# Sheet_B1.net
KiCad netlist of a schematic drawn in Altium Designer
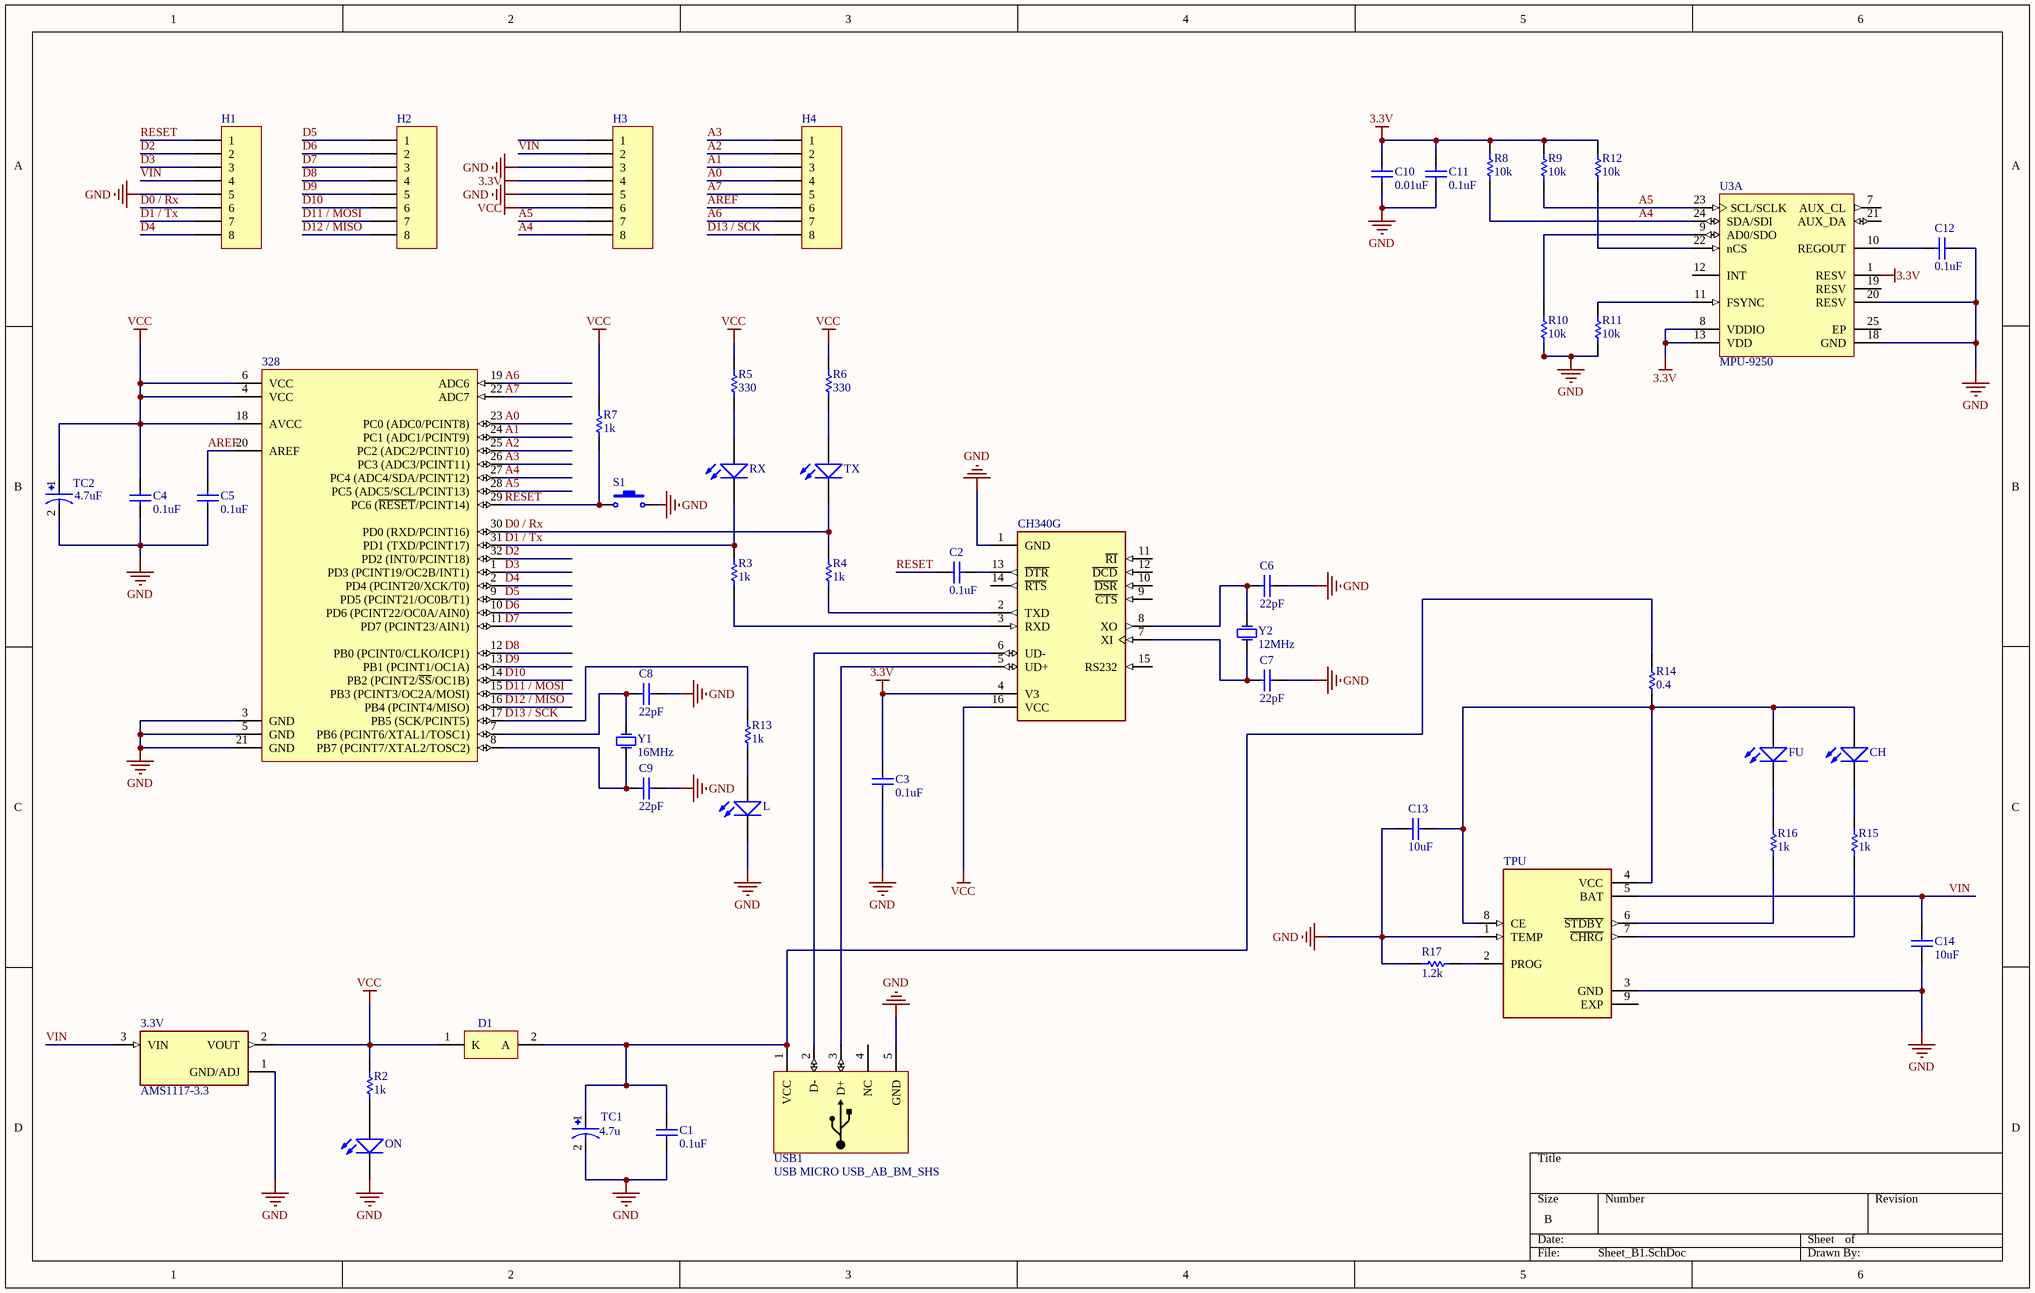
[diagram p0: Sheet_B1.SchDoc]

(export (version "E")
  (design (tool "Eeschema 10.0.6"))
  (components
    (comp (ref "3.3V")
      (value "AMS1117-3.3")
      (footprint "SOT229P700X180-4N")
      (description "Sot223/Pkg 1-Amp 3.3-Volt Low Drop Out Voltage Regulatator")
      (fields (field (name "MF") "Advanced Monolithic Systems"))
      (libsource (lib "AMS1117-3.3") (part "AMS1117-3.3"))
    )
    (comp (ref "328")
      (value "~")
      (footprint "32A_L")
      (libsource (lib "Altium Content Vault") (part "MC-8B-ATM48-SQ32"))
    )
    (comp (ref "C1")
      (value "0.1uF")
      (footprint "CAP0805")
      (description "CAP0805")
      (libsource (lib "CAP0805") (part "CAP0805"))
    )
    (comp (ref "C2")
      (value "0.1uF")
      (footprint "CAP0805")
      (description "CAP0805")
      (libsource (lib "CAP0805") (part "CAP0805"))
    )
    (comp (ref "C3")
      (value "0.1uF")
      (footprint "CAP0805")
      (description "CAP0805")
      (libsource (lib "CAP0805") (part "CAP0805"))
    )
    (comp (ref "C4")
      (value "0.1uF")
      (footprint "CAP0805")
      (description "CAP0805")
      (libsource (lib "CAP0805") (part "CAP0805"))
    )
    (comp (ref "C5")
      (value "0.1uF")
      (footprint "CAP0805")
      (description "CAP0805")
      (libsource (lib "CAP0805") (part "CAP0805"))
    )
    (comp (ref "C6")
      (value "22pF")
      (footprint "CAP0805")
      (description "CAP0805")
      (libsource (lib "CAP0805") (part "CAP0805"))
    )
    (comp (ref "C7")
      (value "22pF")
      (footprint "CAP0805")
      (description "CAP0805")
      (libsource (lib "CAP0805") (part "CAP0805"))
    )
    (comp (ref "C8")
      (value "22pF")
      (footprint "CAP0805")
      (description "CAP0805")
      (libsource (lib "CAP0805") (part "CAP0805"))
    )
    (comp (ref "C9")
      (value "22pF")
      (footprint "CAP0805")
      (description "CAP0805")
      (libsource (lib "CAP0805") (part "CAP0805"))
    )
    (comp (ref "C10")
      (value "0.01uF")
      (footprint "CAP0805")
      (description "CAP0805")
      (libsource (lib "CAP0805") (part "CAP0805"))
    )
    (comp (ref "C11")
      (value "0.1uF")
      (footprint "CAP0805")
      (description "CAP0805")
      (libsource (lib "CAP0805") (part "CAP0805"))
    )
    (comp (ref "C12")
      (value "0.1uF")
      (footprint "CAP0805")
      (description "CAP0805")
      (libsource (lib "CAP0805") (part "CAP0805"))
    )
    (comp (ref "C13")
      (value "10uF")
      (footprint "CAP0805")
      (description "CAP0805")
      (libsource (lib "CAP0805") (part "CAP0805"))
    )
    (comp (ref "C14")
      (value "10uF")
      (footprint "CAP0805")
      (description "CAP0805")
      (libsource (lib "CAP0805") (part "CAP0805"))
    )
    (comp (ref "CH")
      (value "~")
      (footprint "LED_SMD_0805")
      (libsource (lib "LED_SMD_0805") (part "LED_SMD_0805"))
    )
    (comp (ref "CH340G")
      (value "~")
      (footprint "SOIC127P600X180-16N")
      (description "USB Interface Integrated Circuit")
      (fields (field (name "MP") "Ch340G") (field (name "MF") "WCH"))
      (libsource (lib "CH340G") (part "CH340G"))
    )
    (comp (ref "D1")
      (value "~")
      (footprint "ONSC-SMB-2-403A-03_V")
      (description "Schottky Power Rectifier, 2-Pin SMB, Pb-Free, Tape and Reel")
      (fields (field (name "MANUFACTURER") "On Semiconductor") (field (name "PARTNUMBER") "SS24T3G"))
      (libsource (lib "Altium Content Vault") (part "ONSC-D-K1A2-2_A"))
    )
    (comp (ref "FU")
      (value "~")
      (footprint "LED_SMD_0805")
      (libsource (lib "LED_SMD_0805") (part "LED_SMD_0805"))
    )
    (comp (ref "H1") (value "~") (footprint "Header 8") (libsource (lib "Header 8") (part "Header 8")))
    (comp (ref "H2") (value "~") (footprint "Header 8") (libsource (lib "Header 8") (part "Header 8")))
    (comp (ref "H3") (value "~") (footprint "Header 8") (libsource (lib "Header 8") (part "Header 8")))
    (comp (ref "H4") (value "~") (footprint "Header 8") (libsource (lib "Header 8") (part "Header 8")))
    (comp (ref "L")
      (value "~")
      (footprint "LED_SMD_0805")
      (libsource (lib "LED_SMD_0805") (part "LED_SMD_0805"))
    )
    (comp (ref "ON")
      (value "~")
      (footprint "LED_SMD_0805")
      (libsource (lib "LED_SMD_0805") (part "LED_SMD_0805"))
    )
    (comp (ref "R2")
      (value "1k")
      (footprint "RES0805")
      (description "RES0805")
      (libsource (lib "RES0805") (part "RES0805"))
    )
    (comp (ref "R3")
      (value "1k")
      (footprint "RES0805")
      (description "RES0805")
      (libsource (lib "RES0805") (part "RES0805"))
    )
    (comp (ref "R4")
      (value "1k")
      (footprint "RES0805")
      (description "RES0805")
      (libsource (lib "RES0805") (part "RES0805"))
    )
    (comp (ref "R5")
      (value "330")
      (footprint "RES0805")
      (description "RES0805")
      (libsource (lib "RES0805") (part "RES0805"))
    )
    (comp (ref "R6")
      (value "330")
      (footprint "RES0805")
      (description "RES0805")
      (libsource (lib "RES0805") (part "RES0805"))
    )
    (comp (ref "R7")
      (value "1k")
      (footprint "RES0805")
      (description "RES0805")
      (libsource (lib "RES0805") (part "RES0805"))
    )
    (comp (ref "R8")
      (value "10k")
      (footprint "RES0805")
      (description "RES0805")
      (libsource (lib "RES0805") (part "RES0805"))
    )
    (comp (ref "R9")
      (value "10k")
      (footprint "RES0805")
      (description "RES0805")
      (libsource (lib "RES0805") (part "RES0805"))
    )
    (comp (ref "R10")
      (value "10k")
      (footprint "RES0805")
      (description "RES0805")
      (libsource (lib "RES0805") (part "RES0805"))
    )
    (comp (ref "R11")
      (value "10k")
      (footprint "RES0805")
      (description "RES0805")
      (libsource (lib "RES0805") (part "RES0805"))
    )
    (comp (ref "R12")
      (value "10k")
      (footprint "RES0805")
      (description "RES0805")
      (libsource (lib "RES0805") (part "RES0805"))
    )
    (comp (ref "R13")
      (value "1k")
      (footprint "RES0805")
      (description "RES0805")
      (libsource (lib "RES0805") (part "RES0805"))
    )
    (comp (ref "R14")
      (value "0.4")
      (footprint "RES0805")
      (description "RES0805")
      (libsource (lib "RES0805") (part "RES0805"))
    )
    (comp (ref "R15")
      (value "1k")
      (footprint "RES0805")
      (description "RES0805")
      (libsource (lib "RES0805") (part "RES0805"))
    )
    (comp (ref "R16")
      (value "1k")
      (footprint "RES0805")
      (description "RES0805")
      (libsource (lib "RES0805") (part "RES0805"))
    )
    (comp (ref "R17")
      (value "1.2k")
      (footprint "RES0805")
      (description "RES0805")
      (libsource (lib "RES0805") (part "RES0805"))
    )
    (comp (ref "RX")
      (value "~")
      (footprint "LED_SMD_0805")
      (libsource (lib "LED_SMD_0805") (part "LED_SMD_0805"))
    )
    (comp (ref "S1")
      (value "~")
      (footprint "Push Button Switch SMD")
      (libsource (lib "Push Button Switch SMD") (part "Push Button Switch SMD"))
    )
    (comp (ref "TC1")
      (value "4.7u")
      (footprint "CAPMP3516X190N")
      (description "4.7 ÂµF Molded Tantalum Capacitors 25 V 1411 (3528 Metric), 1210 1.5Ohm")
      (fields (field (name "MP") "TAJB475K025RNJ") (field (name "MF") "AVX"))
      (libsource (lib "TAJB475K025RNJ") (part "TAJB475K025RNJ"))
    )
    (comp (ref "TC2")
      (value "4.7uF")
      (footprint "CAPMP3516X190N")
      (description "4.7 ÂµF Molded Tantalum Capacitors 25 V 1411 (3528 Metric), 1210 1.5Ohm")
      (fields (field (name "MP") "TAJB475K025RNJ") (field (name "MF") "AVX"))
      (libsource (lib "TAJB475K025RNJ") (part "TAJB475K025RNJ"))
    )
    (comp (ref "TPU")
      (value "~")
      (footprint "SOIC127P600X175-9N")
      (description "TP4056-42-ESOP8 TP")
      (fields (field (name "MF") "Lite-On Semiconductor") (field (name "MP") "TP4056-42-ESOP8"))
      (libsource (lib "TP4056-42-ESOP8") (part "TP4056-42-ESOP8"))
    )
    (comp (ref "TX")
      (value "~")
      (footprint "LED_SMD_0805")
      (libsource (lib "LED_SMD_0805") (part "LED_SMD_0805"))
    )
    (comp (ref "U3")
      (value "MPU-9250")
      (footprint "INSE-QFN-24-1700X1540TP_M")
      (description "9-axis MotionTracking device, 2.4 to 3,6 V, -40 to 85 degC, 24-Pin QFN, RoHS, Tape and Reel")
      (fields (field (name "MANUFACTURER") "InvenSense"))
      (libsource (lib "Altium Content Vault") (part "INSE-MPU-9250-QFN-24"))
    )
    (comp (ref "USB1")
      (value "USB MICRO USB_AB_BM_SHS")
      (footprint "USB MICRO USB_AB_BM_SHS")
      (libsource (lib "USB MICRO USB_AB_BM_SHS") (part "USB MICRO USB_AB_BM_SHS"))
    )
    (comp (ref "Y1")
      (value "16MHz")
      (footprint "Crystal SMD")
      (description "Crystal SMD")
      (libsource (lib "Crystal SMD") (part "Crystal SMD"))
    )
    (comp (ref "Y2")
      (value "12MHz")
      (footprint "Crystal SMD")
      (description "Crystal SMD")
      (libsource (lib "Crystal SMD") (part "Crystal SMD"))
    )
  )
  (nets
    (net (code "1") (name "/A0") (class "Default")
      (node (ref "328") (pin "23") (pinfunction "PC0_(ADC0/PCINT8)_23") (pintype "bidirectional"))
      (node (ref "H4") (pin "4") (pinfunction "4_4") (pintype "passive"))
    )
    (net (code "2") (name "/A1") (class "Default")
      (node (ref "328") (pin "24") (pinfunction "PC1_(ADC1/PCINT9)_24") (pintype "bidirectional"))
      (node (ref "H4") (pin "3") (pinfunction "3_3") (pintype "passive"))
    )
    (net (code "3") (name "/A2") (class "Default")
      (node (ref "328") (pin "25") (pinfunction "PC2_(ADC2/PCINT10)_25") (pintype "bidirectional"))
      (node (ref "H4") (pin "2") (pinfunction "2_2") (pintype "passive"))
    )
    (net (code "4") (name "/A3") (class "Default")
      (node (ref "328") (pin "26") (pinfunction "PC3_(ADC3/PCINT11)_26") (pintype "bidirectional"))
      (node (ref "H4") (pin "1") (pinfunction "1_1") (pintype "passive"))
    )
    (net (code "5") (name "/A4") (class "Default")
      (node (ref "328") (pin "27") (pinfunction "PC4_(ADC4/SDA/PCINT12)_27") (pintype "bidirectional"))
      (node (ref "H3") (pin "8") (pinfunction "8_8") (pintype "passive"))
      (node (ref "R8") (pin "1") (pinfunction "1_1") (pintype "passive"))
      (node (ref "U3") (pin "24") (pinfunction "SDA/SDI_24") (pintype "bidirectional"))
    )
    (net (code "6") (name "/A5") (class "Default")
      (node (ref "328") (pin "28") (pinfunction "PC5_(ADC5/SCL/PCINT13)_28") (pintype "bidirectional"))
      (node (ref "H3") (pin "7") (pinfunction "7_7") (pintype "passive"))
      (node (ref "R9") (pin "1") (pinfunction "1_1") (pintype "passive"))
      (node (ref "U3") (pin "23") (pinfunction "SCL/SCLK_23") (pintype "input"))
    )
    (net (code "7") (name "/A6") (class "Default")
      (node (ref "328") (pin "19") (pinfunction "ADC6_19") (pintype "input"))
      (node (ref "H4") (pin "7") (pinfunction "7_7") (pintype "passive"))
    )
    (net (code "8") (name "/A7") (class "Default")
      (node (ref "328") (pin "22") (pinfunction "ADC7_22") (pintype "input"))
      (node (ref "H4") (pin "5") (pinfunction "5_5") (pintype "passive"))
    )
    (net (code "9") (name "/AREF") (class "Default")
      (node (ref "328") (pin "20") (pinfunction "AREF_20") (pintype "passive"))
      (node (ref "C5") (pin "2") (pinfunction "2_2") (pintype "passive"))
      (node (ref "H4") (pin "6") (pinfunction "6_6") (pintype "passive"))
    )
    (net (code "10") (name "/D0 {slash} Rx") (class "Default")
      (node (ref "328") (pin "30") (pinfunction "PD0_(RXD/PCINT16)_30") (pintype "bidirectional"))
      (node (ref "H1") (pin "6") (pinfunction "6_6") (pintype "passive"))
      (node (ref "R4") (pin "2") (pinfunction "2_2") (pintype "passive"))
      (node (ref "TX") (pin "1") (pinfunction "K_1") (pintype "passive"))
    )
    (net (code "11") (name "/D1 {slash} Tx") (class "Default")
      (node (ref "328") (pin "31") (pinfunction "PD1_(TXD/PCINT17)_31") (pintype "bidirectional"))
      (node (ref "H1") (pin "7") (pinfunction "7_7") (pintype "passive"))
      (node (ref "R3") (pin "2") (pinfunction "2_2") (pintype "passive"))
      (node (ref "RX") (pin "1") (pinfunction "K_1") (pintype "passive"))
    )
    (net (code "12") (name "/D2") (class "Default")
      (node (ref "328") (pin "32") (pinfunction "PD2_(INT0/PCINT18)_32") (pintype "bidirectional"))
      (node (ref "H1") (pin "2") (pinfunction "2_2") (pintype "passive"))
    )
    (net (code "13") (name "/D3") (class "Default")
      (node (ref "328") (pin "1") (pinfunction "PD3_(PCINT19/OC2B/INT1)_1") (pintype "bidirectional"))
      (node (ref "H1") (pin "3") (pinfunction "3_3") (pintype "passive"))
    )
    (net (code "14") (name "/D4") (class "Default")
      (node (ref "328") (pin "2") (pinfunction "PD4_(PCINT20/XCK/T0)_2") (pintype "bidirectional"))
      (node (ref "H1") (pin "8") (pinfunction "8_8") (pintype "passive"))
    )
    (net (code "15") (name "/D5") (class "Default")
      (node (ref "328") (pin "9") (pinfunction "PD5_(PCINT21/OC0B/T1)_9") (pintype "bidirectional"))
      (node (ref "H2") (pin "1") (pinfunction "1_1") (pintype "passive"))
    )
    (net (code "16") (name "/D6") (class "Default")
      (node (ref "328") (pin "10") (pinfunction "PD6_(PCINT22/OC0A/AIN0)_10") (pintype "bidirectional"))
      (node (ref "H2") (pin "2") (pinfunction "2_2") (pintype "passive"))
    )
    (net (code "17") (name "/D7") (class "Default")
      (node (ref "328") (pin "11") (pinfunction "PD7_(PCINT23/AIN1)_11") (pintype "bidirectional"))
      (node (ref "H2") (pin "3") (pinfunction "3_3") (pintype "passive"))
    )
    (net (code "18") (name "/D8") (class "Default")
      (node (ref "328") (pin "12") (pinfunction "PB0_(PCINT0/CLKO/ICP1)_12") (pintype "bidirectional"))
      (node (ref "H2") (pin "4") (pinfunction "4_4") (pintype "passive"))
    )
    (net (code "19") (name "/D9") (class "Default")
      (node (ref "328") (pin "13") (pinfunction "PB1_(PCINT1/OC1A)_13") (pintype "bidirectional"))
      (node (ref "H2") (pin "5") (pinfunction "5_5") (pintype "passive"))
    )
    (net (code "20") (name "/D10") (class "Default")
      (node (ref "328") (pin "14") (pinfunction "PB2_(PCINT2/~{SS}/OC1B)_14") (pintype "bidirectional"))
      (node (ref "H2") (pin "6") (pinfunction "6_6") (pintype "passive"))
    )
    (net (code "21") (name "/D11 {slash} MOSI") (class "Default")
      (node (ref "328") (pin "15") (pinfunction "PB3_(PCINT3/OC2A/MOSI)_15") (pintype "bidirectional"))
      (node (ref "H2") (pin "7") (pinfunction "7_7") (pintype "passive"))
    )
    (net (code "22") (name "/D12 {slash} MISO") (class "Default")
      (node (ref "328") (pin "16") (pinfunction "PB4_(PCINT4/MISO)_16") (pintype "bidirectional"))
      (node (ref "H2") (pin "8") (pinfunction "8_8") (pintype "passive"))
    )
    (net (code "23") (name "/D13 {slash} SCK") (class "Default")
      (node (ref "328") (pin "17") (pinfunction "PB5_(SCK/PCINT5)_17") (pintype "bidirectional"))
      (node (ref "H4") (pin "8") (pinfunction "8_8") (pintype "passive"))
      (node (ref "R13") (pin "1") (pinfunction "1_1") (pintype "passive"))
    )
    (net (code "24") (name "/RESET") (class "Default")
      (node (ref "328") (pin "29") (pinfunction "PC6_(~{RESET}/PCINT14)_29") (pintype "bidirectional"))
      (node (ref "C2") (pin "2") (pinfunction "2_2") (pintype "passive"))
      (node (ref "H1") (pin "1") (pinfunction "1_1") (pintype "passive"))
      (node (ref "R7") (pin "1") (pinfunction "1_1") (pintype "passive"))
      (node (ref "S1") (pin "1") (pinfunction "1_1") (pintype "passive"))
    )
    (net (code "25") (name "/VIN") (class "Default")
      (node (ref "3.3V") (pin "3") (pinfunction "VIN_3") (pintype "input"))
      (node (ref "C14") (pin "2") (pinfunction "2_2") (pintype "passive"))
      (node (ref "H1") (pin "4") (pinfunction "4_4") (pintype "passive"))
      (node (ref "H3") (pin "2") (pinfunction "2_2") (pintype "passive"))
      (node (ref "TPU") (pin "5") (pinfunction "BAT_5") (pintype "power_in"))
    )
    (net (code "26") (name "3.3V") (class "Default")
      (node (ref "C10") (pin "2") (pinfunction "2_2") (pintype "passive"))
      (node (ref "C11") (pin "2") (pinfunction "2_2") (pintype "passive"))
      (node (ref "C3") (pin "2") (pinfunction "2_2") (pintype "passive"))
      (node (ref "CH340G") (pin "4") (pinfunction "V3_4") (pintype "power_in"))
      (node (ref "H3") (pin "4") (pinfunction "4_4") (pintype "passive"))
      (node (ref "R12") (pin "2") (pinfunction "2_2") (pintype "passive"))
      (node (ref "R8") (pin "2") (pinfunction "2_2") (pintype "passive"))
      (node (ref "R9") (pin "2") (pinfunction "2_2") (pintype "passive"))
      (node (ref "U3") (pin "1") (pinfunction "RESV_1") (pintype "power_in"))
      (node (ref "U3") (pin "13") (pinfunction "VDD_13") (pintype "power_in"))
      (node (ref "U3") (pin "8") (pinfunction "VDDIO_8") (pintype "power_in"))
    )
    (net (code "27") (name "GND") (class "Default")
      (node (ref "3.3V") (pin "1") (pinfunction "GND/ADJ_1") (pintype "power_in"))
      (node (ref "328") (pin "21") (pinfunction "GND_21") (pintype "power_in"))
      (node (ref "328") (pin "3") (pinfunction "GND_3") (pintype "power_in"))
      (node (ref "328") (pin "5") (pinfunction "GND_5") (pintype "power_in"))
      (node (ref "C1") (pin "1") (pinfunction "1_1") (pintype "passive"))
      (node (ref "C10") (pin "1") (pinfunction "1_1") (pintype "passive"))
      (node (ref "C11") (pin "1") (pinfunction "1_1") (pintype "passive"))
      (node (ref "C12") (pin "2") (pinfunction "2_2") (pintype "passive"))
      (node (ref "C13") (pin "2") (pinfunction "2_2") (pintype "passive"))
      (node (ref "C14") (pin "1") (pinfunction "1_1") (pintype "passive"))
      (node (ref "C3") (pin "1") (pinfunction "1_1") (pintype "passive"))
      (node (ref "C4") (pin "2") (pinfunction "2_2") (pintype "passive"))
      (node (ref "C5") (pin "1") (pinfunction "1_1") (pintype "passive"))
      (node (ref "C6") (pin "1") (pinfunction "1_1") (pintype "passive"))
      (node (ref "C7") (pin "1") (pinfunction "1_1") (pintype "passive"))
      (node (ref "C8") (pin "1") (pinfunction "1_1") (pintype "passive"))
      (node (ref "C9") (pin "1") (pinfunction "1_1") (pintype "passive"))
      (node (ref "CH340G") (pin "1") (pinfunction "GND_1") (pintype "power_in"))
      (node (ref "H1") (pin "5") (pinfunction "5_5") (pintype "passive"))
      (node (ref "H3") (pin "3") (pinfunction "3_3") (pintype "passive"))
      (node (ref "H3") (pin "5") (pinfunction "5_5") (pintype "passive"))
      (node (ref "L") (pin "1") (pinfunction "K_1") (pintype "passive"))
      (node (ref "ON") (pin "1") (pinfunction "K_1") (pintype "passive"))
      (node (ref "R10") (pin "2") (pinfunction "2_2") (pintype "passive"))
      (node (ref "R11") (pin "1") (pinfunction "1_1") (pintype "passive"))
      (node (ref "R17") (pin "1") (pinfunction "1_1") (pintype "passive"))
      (node (ref "S1") (pin "2") (pinfunction "2_2") (pintype "passive"))
      (node (ref "TC1") (pin "2") (pinfunction "2_2") (pintype "passive"))
      (node (ref "TC2") (pin "2") (pinfunction "2_2") (pintype "passive"))
      (node (ref "TPU") (pin "1") (pinfunction "TEMP_1") (pintype "input"))
      (node (ref "TPU") (pin "3") (pinfunction "GND_3") (pintype "power_in"))
      (node (ref "U3") (pin "18") (pinfunction "GND_18") (pintype "power_in"))
      (node (ref "U3") (pin "20") (pinfunction "RESV_20") (pintype "power_in"))
      (node (ref "USB1") (pin "5") (pinfunction "GND_5") (pintype "power_in"))
    )
    (net (code "28") (name "Net-(328-PB6_(PCINT6{slash}XTAL1{slash}TOSC1))") (class "Default")
      (node (ref "328") (pin "7") (pinfunction "PB6_(PCINT6/XTAL1/TOSC1)_7") (pintype "bidirectional"))
      (node (ref "C8") (pin "2") (pinfunction "2_2") (pintype "passive"))
      (node (ref "Y1") (pin "2") (pinfunction "OSC2_2") (pintype "passive"))
    )
    (net (code "29") (name "Net-(328-PB7_(PCINT7{slash}XTAL2{slash}TOSC2))") (class "Default")
      (node (ref "328") (pin "8") (pinfunction "PB7_(PCINT7/XTAL2/TOSC2)_8") (pintype "bidirectional"))
      (node (ref "C9") (pin "2") (pinfunction "2_2") (pintype "passive"))
      (node (ref "Y1") (pin "1") (pinfunction "OSC1_1") (pintype "passive"))
    )
    (net (code "30") (name "Net-(CH-A)") (class "Default")
      (node (ref "C13") (pin "1") (pinfunction "1_1") (pintype "passive"))
      (node (ref "CH") (pin "2") (pinfunction "A_2") (pintype "passive"))
      (node (ref "FU") (pin "2") (pinfunction "A_2") (pintype "passive"))
      (node (ref "R14") (pin "1") (pinfunction "1_1") (pintype "passive"))
      (node (ref "TPU") (pin "4") (pinfunction "VCC_4") (pintype "power_in"))
      (node (ref "TPU") (pin "8") (pinfunction "CE_8") (pintype "input"))
    )
    (net (code "31") (name "Net-(CH-K)") (class "Default")
      (node (ref "CH") (pin "1") (pinfunction "K_1") (pintype "passive"))
      (node (ref "R15") (pin "1") (pinfunction "1_1") (pintype "passive"))
    )
    (net (code "32") (name "Net-(CH340G-RXD)") (class "Default")
      (node (ref "CH340G") (pin "3") (pinfunction "RXD_3") (pintype "input"))
      (node (ref "R3") (pin "1") (pinfunction "1_1") (pintype "passive"))
    )
    (net (code "33") (name "Net-(CH340G-TXD)") (class "Default")
      (node (ref "CH340G") (pin "2") (pinfunction "TXD_2") (pintype "output"))
      (node (ref "R4") (pin "1") (pinfunction "1_1") (pintype "passive"))
    )
    (net (code "34") (name "Net-(CH340G-UD+)") (class "Default")
      (node (ref "CH340G") (pin "5") (pinfunction "UD+_5") (pintype "bidirectional"))
      (node (ref "USB1") (pin "3") (pinfunction "D+_3") (pintype "bidirectional"))
    )
    (net (code "35") (name "Net-(CH340G-UD-)") (class "Default")
      (node (ref "CH340G") (pin "6") (pinfunction "UD-_6") (pintype "bidirectional"))
      (node (ref "USB1") (pin "2") (pinfunction "D-_2") (pintype "bidirectional"))
    )
    (net (code "36") (name "Net-(CH340G-XI)") (class "Default")
      (node (ref "C7") (pin "2") (pinfunction "2_2") (pintype "passive"))
      (node (ref "CH340G") (pin "7") (pinfunction "XI_7") (pintype "input"))
      (node (ref "Y2") (pin "1") (pinfunction "OSC1_1") (pintype "passive"))
    )
    (net (code "37") (name "Net-(CH340G-XO)") (class "Default")
      (node (ref "C6") (pin "2") (pinfunction "2_2") (pintype "passive"))
      (node (ref "CH340G") (pin "8") (pinfunction "XO_8") (pintype "output"))
      (node (ref "Y2") (pin "2") (pinfunction "OSC2_2") (pintype "passive"))
    )
    (net (code "38") (name "Net-(CH340G-~{DTR})") (class "Default")
      (node (ref "C2") (pin "1") (pinfunction "1_1") (pintype "passive"))
      (node (ref "CH340G") (pin "13") (pinfunction "~{DTR}_13") (pintype "output"))
    )
    (net (code "39") (name "Net-(D1-A)") (class "Default")
      (node (ref "C1") (pin "2") (pinfunction "2_2") (pintype "passive"))
      (node (ref "D1") (pin "2") (pinfunction "A_2") (pintype "passive"))
      (node (ref "R14") (pin "2") (pinfunction "2_2") (pintype "passive"))
      (node (ref "TC1") (pin "1") (pinfunction "1_1") (pintype "passive"))
      (node (ref "USB1") (pin "1") (pinfunction "VCC_1") (pintype "power_in"))
    )
    (net (code "40") (name "Net-(FU-K)") (class "Default")
      (node (ref "FU") (pin "1") (pinfunction "K_1") (pintype "passive"))
      (node (ref "R16") (pin "2") (pinfunction "2_2") (pintype "passive"))
    )
    (net (code "41") (name "Net-(L-A)") (class "Default")
      (node (ref "L") (pin "2") (pinfunction "A_2") (pintype "passive"))
      (node (ref "R13") (pin "2") (pinfunction "2_2") (pintype "passive"))
    )
    (net (code "42") (name "Net-(ON-A)") (class "Default")
      (node (ref "ON") (pin "2") (pinfunction "A_2") (pintype "passive"))
      (node (ref "R2") (pin "1") (pinfunction "1_1") (pintype "passive"))
    )
    (net (code "43") (name "Net-(RX-A)") (class "Default")
      (node (ref "R5") (pin "1") (pinfunction "1_1") (pintype "passive"))
      (node (ref "RX") (pin "2") (pinfunction "A_2") (pintype "passive"))
    )
    (net (code "44") (name "Net-(TPU-PROG)") (class "Default")
      (node (ref "R17") (pin "2") (pinfunction "2_2") (pintype "passive"))
      (node (ref "TPU") (pin "2") (pinfunction "PROG_2") (pintype "passive"))
    )
    (net (code "45") (name "Net-(TPU-~{CHRG})") (class "Default")
      (node (ref "R15") (pin "2") (pinfunction "2_2") (pintype "passive"))
      (node (ref "TPU") (pin "7") (pinfunction "~{CHRG}_7") (pintype "output"))
    )
    (net (code "46") (name "Net-(TPU-~{STDBY})") (class "Default")
      (node (ref "R16") (pin "1") (pinfunction "1_1") (pintype "passive"))
      (node (ref "TPU") (pin "6") (pinfunction "~{STDBY}_6") (pintype "output"))
    )
    (net (code "47") (name "Net-(TX-A)") (class "Default")
      (node (ref "R6") (pin "1") (pinfunction "1_1") (pintype "passive"))
      (node (ref "TX") (pin "2") (pinfunction "A_2") (pintype "passive"))
    )
    (net (code "48") (name "Net-(U3A-AD0{slash}SDO)") (class "Default")
      (node (ref "R10") (pin "1") (pinfunction "1_1") (pintype "passive"))
      (node (ref "U3") (pin "9") (pinfunction "AD0/SDO_9") (pintype "bidirectional"))
    )
    (net (code "49") (name "Net-(U3A-FSYNC)") (class "Default")
      (node (ref "R11") (pin "2") (pinfunction "2_2") (pintype "passive"))
      (node (ref "U3") (pin "11") (pinfunction "FSYNC_11") (pintype "input"))
    )
    (net (code "50") (name "Net-(U3A-REGOUT)") (class "Default")
      (node (ref "C12") (pin "1") (pinfunction "1_1") (pintype "passive"))
      (node (ref "U3") (pin "10") (pinfunction "REGOUT_10") (pintype "passive"))
    )
    (net (code "51") (name "Net-(U3A-nCS)") (class "Default")
      (node (ref "R12") (pin "1") (pinfunction "1_1") (pintype "passive"))
      (node (ref "U3") (pin "22") (pinfunction "nCS_22") (pintype "input"))
    )
    (net (code "52") (name "VCC") (class "Default")
      (node (ref "3.3V") (pin "2") (pinfunction "VOUT_2") (pintype "output"))
      (node (ref "328") (pin "18") (pinfunction "AVCC_18") (pintype "power_in"))
      (node (ref "328") (pin "4") (pinfunction "VCC_4") (pintype "power_in"))
      (node (ref "328") (pin "6") (pinfunction "VCC_6") (pintype "power_in"))
      (node (ref "C4") (pin "1") (pinfunction "1_1") (pintype "passive"))
      (node (ref "CH340G") (pin "16") (pinfunction "VCC_16") (pintype "power_in"))
      (node (ref "D1") (pin "1") (pinfunction "K_1") (pintype "passive"))
      (node (ref "H3") (pin "6") (pinfunction "6_6") (pintype "passive"))
      (node (ref "R2") (pin "2") (pinfunction "2_2") (pintype "passive"))
      (node (ref "R5") (pin "2") (pinfunction "2_2") (pintype "passive"))
      (node (ref "R6") (pin "2") (pinfunction "2_2") (pintype "passive"))
      (node (ref "R7") (pin "2") (pinfunction "2_2") (pintype "passive"))
      (node (ref "TC2") (pin "1") (pinfunction "1_1") (pintype "passive"))
    )
    (net (code "53") (name "unconnected-(CH340G-RS232-Pad15)") (class "Default")
      (node (ref "CH340G") (pin "15") (pinfunction "RS232_15") (pintype "input"))
    )
    (net (code "54") (name "unconnected-(CH340G-~{CTS}-Pad9)") (class "Default")
      (node (ref "CH340G") (pin "9") (pinfunction "~{CTS}_9") (pintype "input"))
    )
    (net (code "55") (name "unconnected-(CH340G-~{DCD}-Pad12)") (class "Default")
      (node (ref "CH340G") (pin "12") (pinfunction "~{DCD}_12") (pintype "input"))
    )
    (net (code "56") (name "unconnected-(CH340G-~{DSR}-Pad10)") (class "Default")
      (node (ref "CH340G") (pin "10") (pinfunction "~{DSR}_10") (pintype "input"))
    )
    (net (code "57") (name "unconnected-(CH340G-~{RI}-Pad11)") (class "Default")
      (node (ref "CH340G") (pin "11") (pinfunction "~{RI}_11") (pintype "input"))
    )
    (net (code "58") (name "unconnected-(CH340G-~{RTS}-Pad14)") (class "Default")
      (node (ref "CH340G") (pin "14") (pinfunction "~{RTS}_14") (pintype "output"))
    )
    (net (code "59") (name "unconnected-(H3-Pad1)") (class "Default")
      (node (ref "H3") (pin "1") (pinfunction "1_1") (pintype "passive"))
    )
    (net (code "60") (name "unconnected-(TPU-EXP-Pad9)") (class "Default")
      (node (ref "TPU") (pin "9") (pinfunction "EXP_9") (pintype "passive"))
    )
    (net (code "61") (name "unconnected-(U3A-AUX_CL-Pad7)") (class "Default")
      (node (ref "U3") (pin "7") (pinfunction "AUX_CL_7") (pintype "output"))
    )
    (net (code "62") (name "unconnected-(U3A-AUX_DA-Pad21)") (class "Default")
      (node (ref "U3") (pin "21") (pinfunction "AUX_DA_21") (pintype "bidirectional"))
    )
    (net (code "63") (name "unconnected-(U3A-EP-Pad25)") (class "Default")
      (node (ref "U3") (pin "25") (pinfunction "EP_25") (pintype "passive"))
    )
    (net (code "64") (name "unconnected-(U3A-INT-Pad12)") (class "Default")
      (node (ref "U3") (pin "12") (pinfunction "INT_12") (pintype "tri_state"))
    )
    (net (code "65") (name "unconnected-(U3A-RESV-Pad19)") (class "Default")
      (node (ref "U3") (pin "19") (pinfunction "RESV_19") (pintype "passive"))
    )
    (net (code "66") (name "unconnected-(USB1-NC-Pad4)") (class "Default")
      (node (ref "USB1") (pin "4") (pinfunction "NC_4") (pintype "passive"))
    )
  )
)
